# 07_FUNCTION_EFUSE.net
KiCad netlist of a schematic drawn in Altium Designer
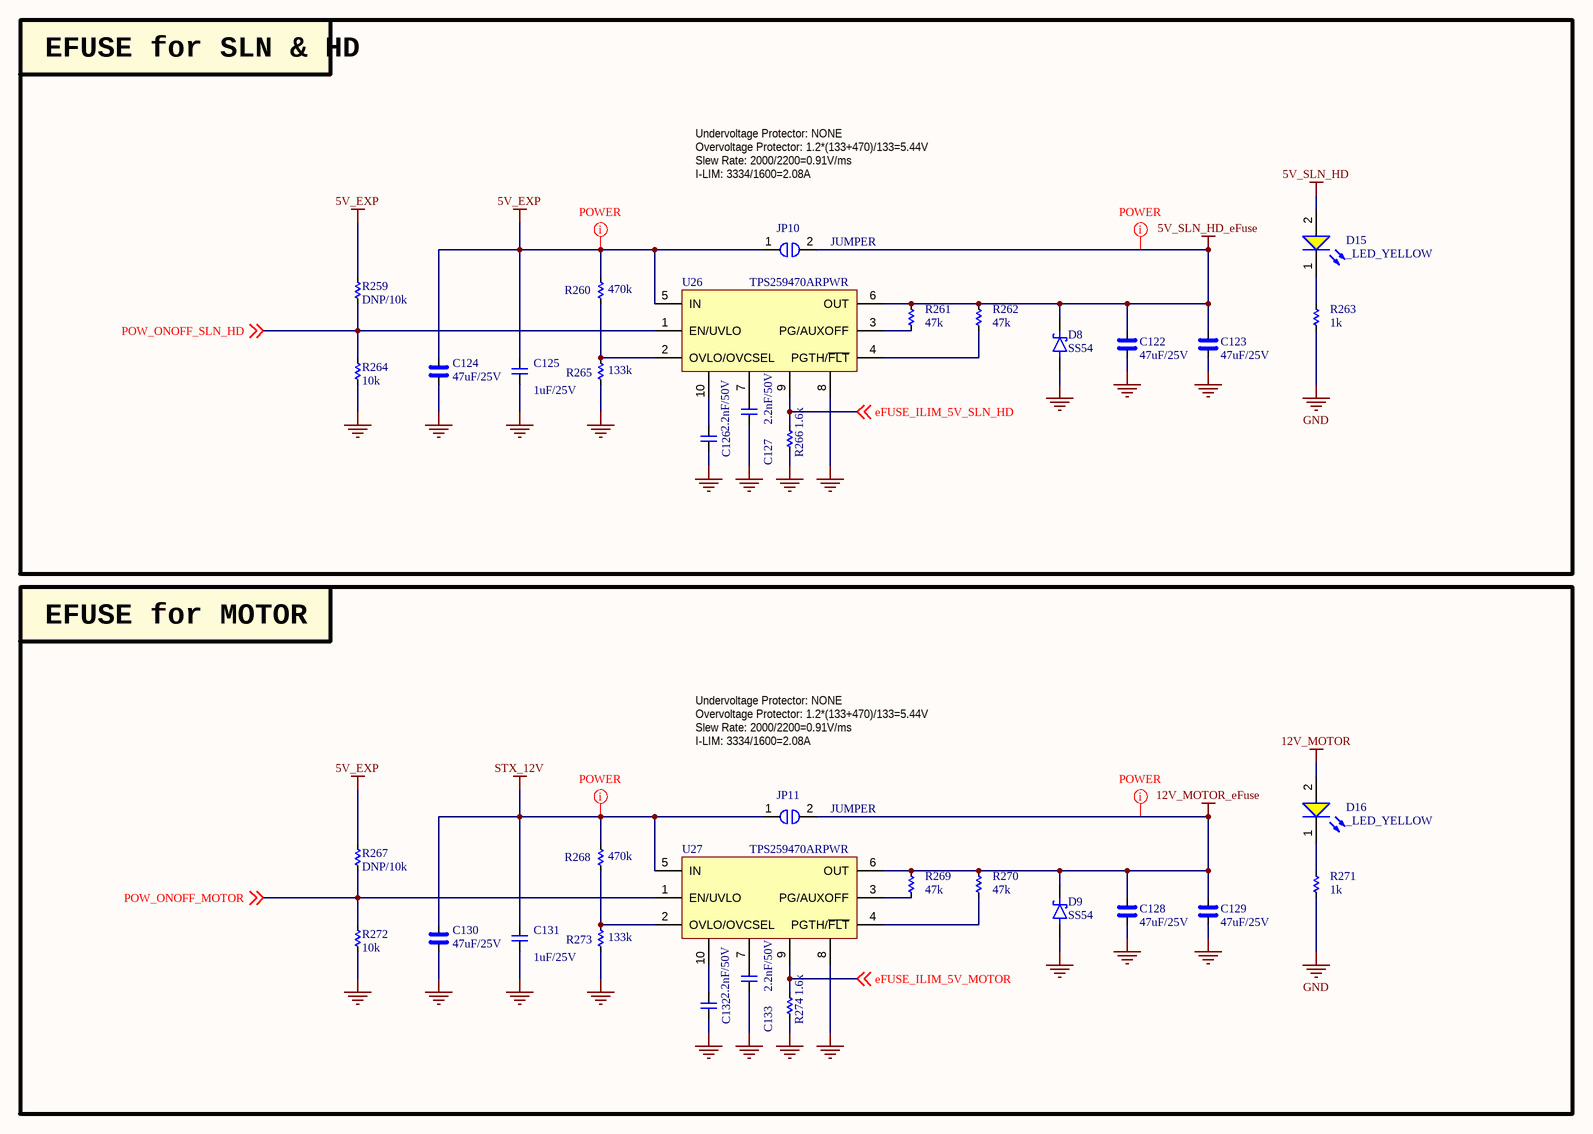
[diagram p0: 07_FUNCTION_EFUSE.SchDoc]

(export (version "E")
  (design (tool "Eeschema 10.0.6"))
  (components
    (comp (ref "C122")
      (value "47uF/25V")
      (footprint "CAP_C_3225X80")
      (description "CAP High Value")
      (libsource (lib "LABLIB") (part "_CAP_C_High_2"))
    )
    (comp (ref "C123")
      (value "47uF/25V")
      (footprint "CAP_C_3225X80")
      (description "CAP High Value")
      (libsource (lib "LABLIB") (part "_CAP_C_High_2"))
    )
    (comp (ref "C124")
      (value "47uF/25V")
      (footprint "CAP_C_3225X80")
      (description "CAP High Value")
      (libsource (lib "LABLIB") (part "_CAP_C_High_2"))
    )
    (comp (ref "C125")
      (value "1uF/25V")
      (footprint "CAP_C_1005X60")
      (description "CAP")
      (libsource (lib "LABLIB") (part "_CAP_C_2"))
    )
    (comp (ref "C126")
      (value "2.2nF/50V")
      (footprint "CAP_C_1005X60")
      (description "CAP")
      (libsource (lib "LABLIB") (part "_CAP_C_2"))
    )
    (comp (ref "C127")
      (value "2.2nF/50V")
      (footprint "CAP_C_1005X60")
      (description "CAP")
      (libsource (lib "LABLIB") (part "_CAP_C_2"))
    )
    (comp (ref "C128")
      (value "47uF/25V")
      (footprint "CAP_C_3225X80")
      (description "CAP High Value")
      (libsource (lib "LABLIB") (part "_CAP_C_High_2"))
    )
    (comp (ref "C129")
      (value "47uF/25V")
      (footprint "CAP_C_3225X80")
      (description "CAP High Value")
      (libsource (lib "LABLIB") (part "_CAP_C_High_2"))
    )
    (comp (ref "C130")
      (value "47uF/25V")
      (footprint "CAP_C_3225X80")
      (description "CAP High Value")
      (libsource (lib "LABLIB") (part "_CAP_C_High_2"))
    )
    (comp (ref "C131")
      (value "1uF/25V")
      (footprint "CAP_C_1005X60")
      (description "CAP")
      (libsource (lib "LABLIB") (part "_CAP_C_2"))
    )
    (comp (ref "C132")
      (value "2.2nF/50V")
      (footprint "CAP_C_1005X60")
      (description "CAP")
      (libsource (lib "LABLIB") (part "_CAP_C_2"))
    )
    (comp (ref "C133")
      (value "2.2nF/50V")
      (footprint "CAP_C_1005X60")
      (description "CAP")
      (libsource (lib "LABLIB") (part "_CAP_C_2"))
    )
    (comp (ref "D8")
      (value "SS54")
      (footprint "DO-214AC_SMA")
      (description "DIODE SCHOTTKY")
      (libsource (lib "LABLIB") (part "DIODE SCHOTTKY"))
    )
    (comp (ref "D9")
      (value "SS54")
      (footprint "DO-214AC_SMA")
      (description "DIODE SCHOTTKY")
      (libsource (lib "LABLIB") (part "DIODE SCHOTTKY"))
    )
    (comp (ref "D15")
      (value "_LED_YELLOW")
      (footprint "LED_0603")
      (libsource (lib "LABLIB") (part "_LED_YELLOW"))
    )
    (comp (ref "D16")
      (value "_LED_YELLOW")
      (footprint "LED_0603")
      (libsource (lib "LABLIB") (part "_LED_YELLOW"))
    )
    (comp (ref "JP10")
      (value "JUMPER")
      (footprint "JUMPER_1608")
      (libsource (lib "BEE-DAL_EXP_sche") (part "JUMPER_1_1"))
    )
    (comp (ref "JP11")
      (value "JUMPER")
      (footprint "JUMPER_1608")
      (libsource (lib "BEE-DAL_EXP_sche") (part "JUMPER_1_1"))
    )
    (comp (ref "R259")
      (value "DNP/10k")
      (footprint "RES_C_1005X40")
      (description "RES")
      (libsource (lib "LABLIB") (part "_RES_B_2"))
    )
    (comp (ref "R260")
      (value "470k")
      (footprint "RES_C_1005X40")
      (description "RES")
      (libsource (lib "LABLIB") (part "_RES_B_2"))
    )
    (comp (ref "R261")
      (value "47k")
      (footprint "RES_C_1005X40")
      (description "RES")
      (libsource (lib "LABLIB") (part "_RES_B_2"))
    )
    (comp (ref "R262")
      (value "47k")
      (footprint "RES_C_1005X40")
      (description "RES")
      (libsource (lib "LABLIB") (part "_RES_B_2"))
    )
    (comp (ref "R263")
      (value "1k")
      (footprint "RES_C_1005X40")
      (description "RES")
      (libsource (lib "LABLIB") (part "_RES_B_2"))
    )
    (comp (ref "R264")
      (value "10k")
      (footprint "RES_C_1005X40")
      (description "RES")
      (libsource (lib "LABLIB") (part "_RES_B_2"))
    )
    (comp (ref "R265")
      (value "133k")
      (footprint "RES_C_1005X40")
      (description "RES")
      (libsource (lib "LABLIB") (part "_RES_B_2"))
    )
    (comp (ref "R266")
      (value "1.6k")
      (footprint "RES_C_1005X40")
      (description "RES")
      (libsource (lib "LABLIB") (part "_RES_B_2"))
    )
    (comp (ref "R267")
      (value "DNP/10k")
      (footprint "RES_C_1005X40")
      (description "RES")
      (libsource (lib "LABLIB") (part "_RES_B_2"))
    )
    (comp (ref "R268")
      (value "470k")
      (footprint "RES_C_1005X40")
      (description "RES")
      (libsource (lib "LABLIB") (part "_RES_B_2"))
    )
    (comp (ref "R269")
      (value "47k")
      (footprint "RES_C_1005X40")
      (description "RES")
      (libsource (lib "LABLIB") (part "_RES_B_2"))
    )
    (comp (ref "R270")
      (value "47k")
      (footprint "RES_C_1005X40")
      (description "RES")
      (libsource (lib "LABLIB") (part "_RES_B_2"))
    )
    (comp (ref "R271")
      (value "1k")
      (footprint "RES_C_1005X40")
      (description "RES")
      (libsource (lib "LABLIB") (part "_RES_B_2"))
    )
    (comp (ref "R272")
      (value "10k")
      (footprint "RES_C_1005X40")
      (description "RES")
      (libsource (lib "LABLIB") (part "_RES_B_2"))
    )
    (comp (ref "R273")
      (value "133k")
      (footprint "RES_C_1005X40")
      (description "RES")
      (libsource (lib "LABLIB") (part "_RES_B_2"))
    )
    (comp (ref "R274")
      (value "1.6k")
      (footprint "RES_C_1005X40")
      (description "RES")
      (libsource (lib "LABLIB") (part "_RES_B_2"))
    )
    (comp (ref "U26")
      (value "TPS259470ARPWR")
      (footprint "VQFN-HR-10")
      (libsource (lib "BEE-DAL_EXP_sche") (part "TPS259470ARPWR"))
    )
    (comp (ref "U27")
      (value "TPS259470ARPWR")
      (footprint "VQFN-HR-10")
      (libsource (lib "BEE-DAL_EXP_sche") (part "TPS259470ARPWR"))
    )
  )
  (nets
    (net (code "1") (name "5V_EXP") (class "Default")
      (node (ref "C124") (pin "2") (pinfunction "2_2") (pintype "passive"))
      (node (ref "C125") (pin "2") (pinfunction "2_2") (pintype "passive"))
      (node (ref "JP10") (pin "1") (pinfunction "1_1") (pintype "passive"))
      (node (ref "R259") (pin "1") (pinfunction "1_1") (pintype "passive"))
      (node (ref "R260") (pin "2") (pinfunction "2_2") (pintype "passive"))
      (node (ref "R267") (pin "1") (pinfunction "1_1") (pintype "passive"))
      (node (ref "U26") (pin "5") (pinfunction "IN_5") (pintype "passive"))
    )
    (net (code "2") (name "5V_SLN_HD") (class "Default")
      (node (ref "D15") (pin "2") (pinfunction "A_2") (pintype "passive"))
    )
    (net (code "3") (name "5V_SLN_HD_eFuse") (class "Default")
      (node (ref "C122") (pin "2") (pinfunction "2_2") (pintype "passive"))
      (node (ref "C123") (pin "2") (pinfunction "2_2") (pintype "passive"))
      (node (ref "D8") (pin "1") (pinfunction "K_1") (pintype "passive"))
      (node (ref "JP10") (pin "2") (pinfunction "2_2") (pintype "passive"))
      (node (ref "R261") (pin "2") (pinfunction "2_2") (pintype "passive"))
      (node (ref "R262") (pin "2") (pinfunction "2_2") (pintype "passive"))
      (node (ref "U26") (pin "6") (pinfunction "OUT_6") (pintype "passive"))
    )
    (net (code "4") (name "12V_MOTOR") (class "Default")
      (node (ref "D16") (pin "2") (pinfunction "A_2") (pintype "passive"))
    )
    (net (code "5") (name "12V_MOTOR_eFuse") (class "Default")
      (node (ref "C128") (pin "2") (pinfunction "2_2") (pintype "passive"))
      (node (ref "C129") (pin "2") (pinfunction "2_2") (pintype "passive"))
      (node (ref "D9") (pin "1") (pinfunction "K_1") (pintype "passive"))
      (node (ref "JP11") (pin "2") (pinfunction "2_2") (pintype "passive"))
      (node (ref "R269") (pin "2") (pinfunction "2_2") (pintype "passive"))
      (node (ref "R270") (pin "2") (pinfunction "2_2") (pintype "passive"))
      (node (ref "U27") (pin "6") (pinfunction "OUT_6") (pintype "passive"))
    )
    (net (code "6") (name "GND") (class "Default")
      (node (ref "C122") (pin "1") (pinfunction "1_1") (pintype "passive"))
      (node (ref "C123") (pin "1") (pinfunction "1_1") (pintype "passive"))
      (node (ref "C124") (pin "1") (pinfunction "1_1") (pintype "passive"))
      (node (ref "C125") (pin "1") (pinfunction "1_1") (pintype "passive"))
      (node (ref "C126") (pin "1") (pinfunction "1_1") (pintype "passive"))
      (node (ref "C127") (pin "1") (pinfunction "1_1") (pintype "passive"))
      (node (ref "C128") (pin "1") (pinfunction "1_1") (pintype "passive"))
      (node (ref "C129") (pin "1") (pinfunction "1_1") (pintype "passive"))
      (node (ref "C130") (pin "1") (pinfunction "1_1") (pintype "passive"))
      (node (ref "C131") (pin "1") (pinfunction "1_1") (pintype "passive"))
      (node (ref "C132") (pin "1") (pinfunction "1_1") (pintype "passive"))
      (node (ref "C133") (pin "1") (pinfunction "1_1") (pintype "passive"))
      (node (ref "D8") (pin "2") (pinfunction "A_2") (pintype "passive"))
      (node (ref "D9") (pin "2") (pinfunction "A_2") (pintype "passive"))
      (node (ref "R263") (pin "1") (pinfunction "1_1") (pintype "passive"))
      (node (ref "R264") (pin "2") (pinfunction "2_2") (pintype "passive"))
      (node (ref "R265") (pin "1") (pinfunction "1_1") (pintype "passive"))
      (node (ref "R266") (pin "1") (pinfunction "1_1") (pintype "passive"))
      (node (ref "R271") (pin "1") (pinfunction "1_1") (pintype "passive"))
      (node (ref "R272") (pin "2") (pinfunction "2_2") (pintype "passive"))
      (node (ref "R273") (pin "1") (pinfunction "1_1") (pintype "passive"))
      (node (ref "R274") (pin "1") (pinfunction "1_1") (pintype "passive"))
      (node (ref "U26") (pin "8") (pinfunction "8_8") (pintype "passive"))
      (node (ref "U27") (pin "8") (pinfunction "8_8") (pintype "passive"))
    )
    (net (code "7") (name "Net-(C126-Pad2)") (class "Default")
      (node (ref "C126") (pin "2") (pinfunction "2_2") (pintype "passive"))
      (node (ref "U26") (pin "10") (pinfunction "10_10") (pintype "passive"))
    )
    (net (code "8") (name "Net-(C127-Pad2)") (class "Default")
      (node (ref "C127") (pin "2") (pinfunction "2_2") (pintype "passive"))
      (node (ref "U26") (pin "7") (pinfunction "7_7") (pintype "passive"))
    )
    (net (code "9") (name "Net-(C132-Pad2)") (class "Default")
      (node (ref "C132") (pin "2") (pinfunction "2_2") (pintype "passive"))
      (node (ref "U27") (pin "10") (pinfunction "10_10") (pintype "passive"))
    )
    (net (code "10") (name "Net-(C133-Pad2)") (class "Default")
      (node (ref "C133") (pin "2") (pinfunction "2_2") (pintype "passive"))
      (node (ref "U27") (pin "7") (pinfunction "7_7") (pintype "passive"))
    )
    (net (code "11") (name "Net-(D15-K)") (class "Default")
      (node (ref "D15") (pin "1") (pinfunction "K_1") (pintype "passive"))
      (node (ref "R263") (pin "2") (pinfunction "2_2") (pintype "passive"))
    )
    (net (code "12") (name "Net-(D16-K)") (class "Default")
      (node (ref "D16") (pin "1") (pinfunction "K_1") (pintype "passive"))
      (node (ref "R271") (pin "2") (pinfunction "2_2") (pintype "passive"))
    )
    (net (code "13") (name "Net-(U26-OVLO{slash}OVCSEL)") (class "Default")
      (node (ref "R260") (pin "1") (pinfunction "1_1") (pintype "passive"))
      (node (ref "R265") (pin "2") (pinfunction "2_2") (pintype "passive"))
      (node (ref "U26") (pin "2") (pinfunction "OVLO/OVCSEL_2") (pintype "passive"))
    )
    (net (code "14") (name "Net-(U26-PGTH{slash}~{FLT})") (class "Default")
      (node (ref "R262") (pin "1") (pinfunction "1_1") (pintype "passive"))
      (node (ref "U26") (pin "4") (pinfunction "PGTH/~{FLT}_4") (pintype "passive"))
    )
    (net (code "15") (name "Net-(U26-PG{slash}AUXOFF)") (class "Default")
      (node (ref "R261") (pin "1") (pinfunction "1_1") (pintype "passive"))
      (node (ref "U26") (pin "3") (pinfunction "PG/AUXOFF_3") (pintype "passive"))
    )
    (net (code "16") (name "Net-(U27-OVLO{slash}OVCSEL)") (class "Default")
      (node (ref "R268") (pin "1") (pinfunction "1_1") (pintype "passive"))
      (node (ref "R273") (pin "2") (pinfunction "2_2") (pintype "passive"))
      (node (ref "U27") (pin "2") (pinfunction "OVLO/OVCSEL_2") (pintype "passive"))
    )
    (net (code "17") (name "Net-(U27-PGTH{slash}~{FLT})") (class "Default")
      (node (ref "R270") (pin "1") (pinfunction "1_1") (pintype "passive"))
      (node (ref "U27") (pin "4") (pinfunction "PGTH/~{FLT}_4") (pintype "passive"))
    )
    (net (code "18") (name "Net-(U27-PG{slash}AUXOFF)") (class "Default")
      (node (ref "R269") (pin "1") (pinfunction "1_1") (pintype "passive"))
      (node (ref "U27") (pin "3") (pinfunction "PG/AUXOFF_3") (pintype "passive"))
    )
    (net (code "19") (name "POW_ONOFF_MOTOR") (class "Default")
      (node (ref "R267") (pin "2") (pinfunction "2_2") (pintype "passive"))
      (node (ref "R272") (pin "1") (pinfunction "1_1") (pintype "passive"))
      (node (ref "U27") (pin "1") (pinfunction "EN/UVLO_1") (pintype "passive"))
    )
    (net (code "20") (name "POW_ONOFF_SLN_HD") (class "Default")
      (node (ref "R259") (pin "2") (pinfunction "2_2") (pintype "passive"))
      (node (ref "R264") (pin "1") (pinfunction "1_1") (pintype "passive"))
      (node (ref "U26") (pin "1") (pinfunction "EN/UVLO_1") (pintype "passive"))
    )
    (net (code "21") (name "STX_12V") (class "Default")
      (node (ref "C130") (pin "2") (pinfunction "2_2") (pintype "passive"))
      (node (ref "C131") (pin "2") (pinfunction "2_2") (pintype "passive"))
      (node (ref "JP11") (pin "1") (pinfunction "1_1") (pintype "passive"))
      (node (ref "R268") (pin "2") (pinfunction "2_2") (pintype "passive"))
      (node (ref "U27") (pin "5") (pinfunction "IN_5") (pintype "passive"))
    )
    (net (code "22") (name "eFUSE_ILIM_5V_MOTOR") (class "Default")
      (node (ref "R274") (pin "2") (pinfunction "2_2") (pintype "passive"))
      (node (ref "U27") (pin "9") (pinfunction "9_9") (pintype "passive"))
    )
    (net (code "23") (name "eFUSE_ILIM_5V_SLN_HD") (class "Default")
      (node (ref "R266") (pin "2") (pinfunction "2_2") (pintype "passive"))
      (node (ref "U26") (pin "9") (pinfunction "9_9") (pintype "passive"))
    )
  )
)
